# BuckConverter.net
KiCad netlist of a schematic drawn in Altium Designer
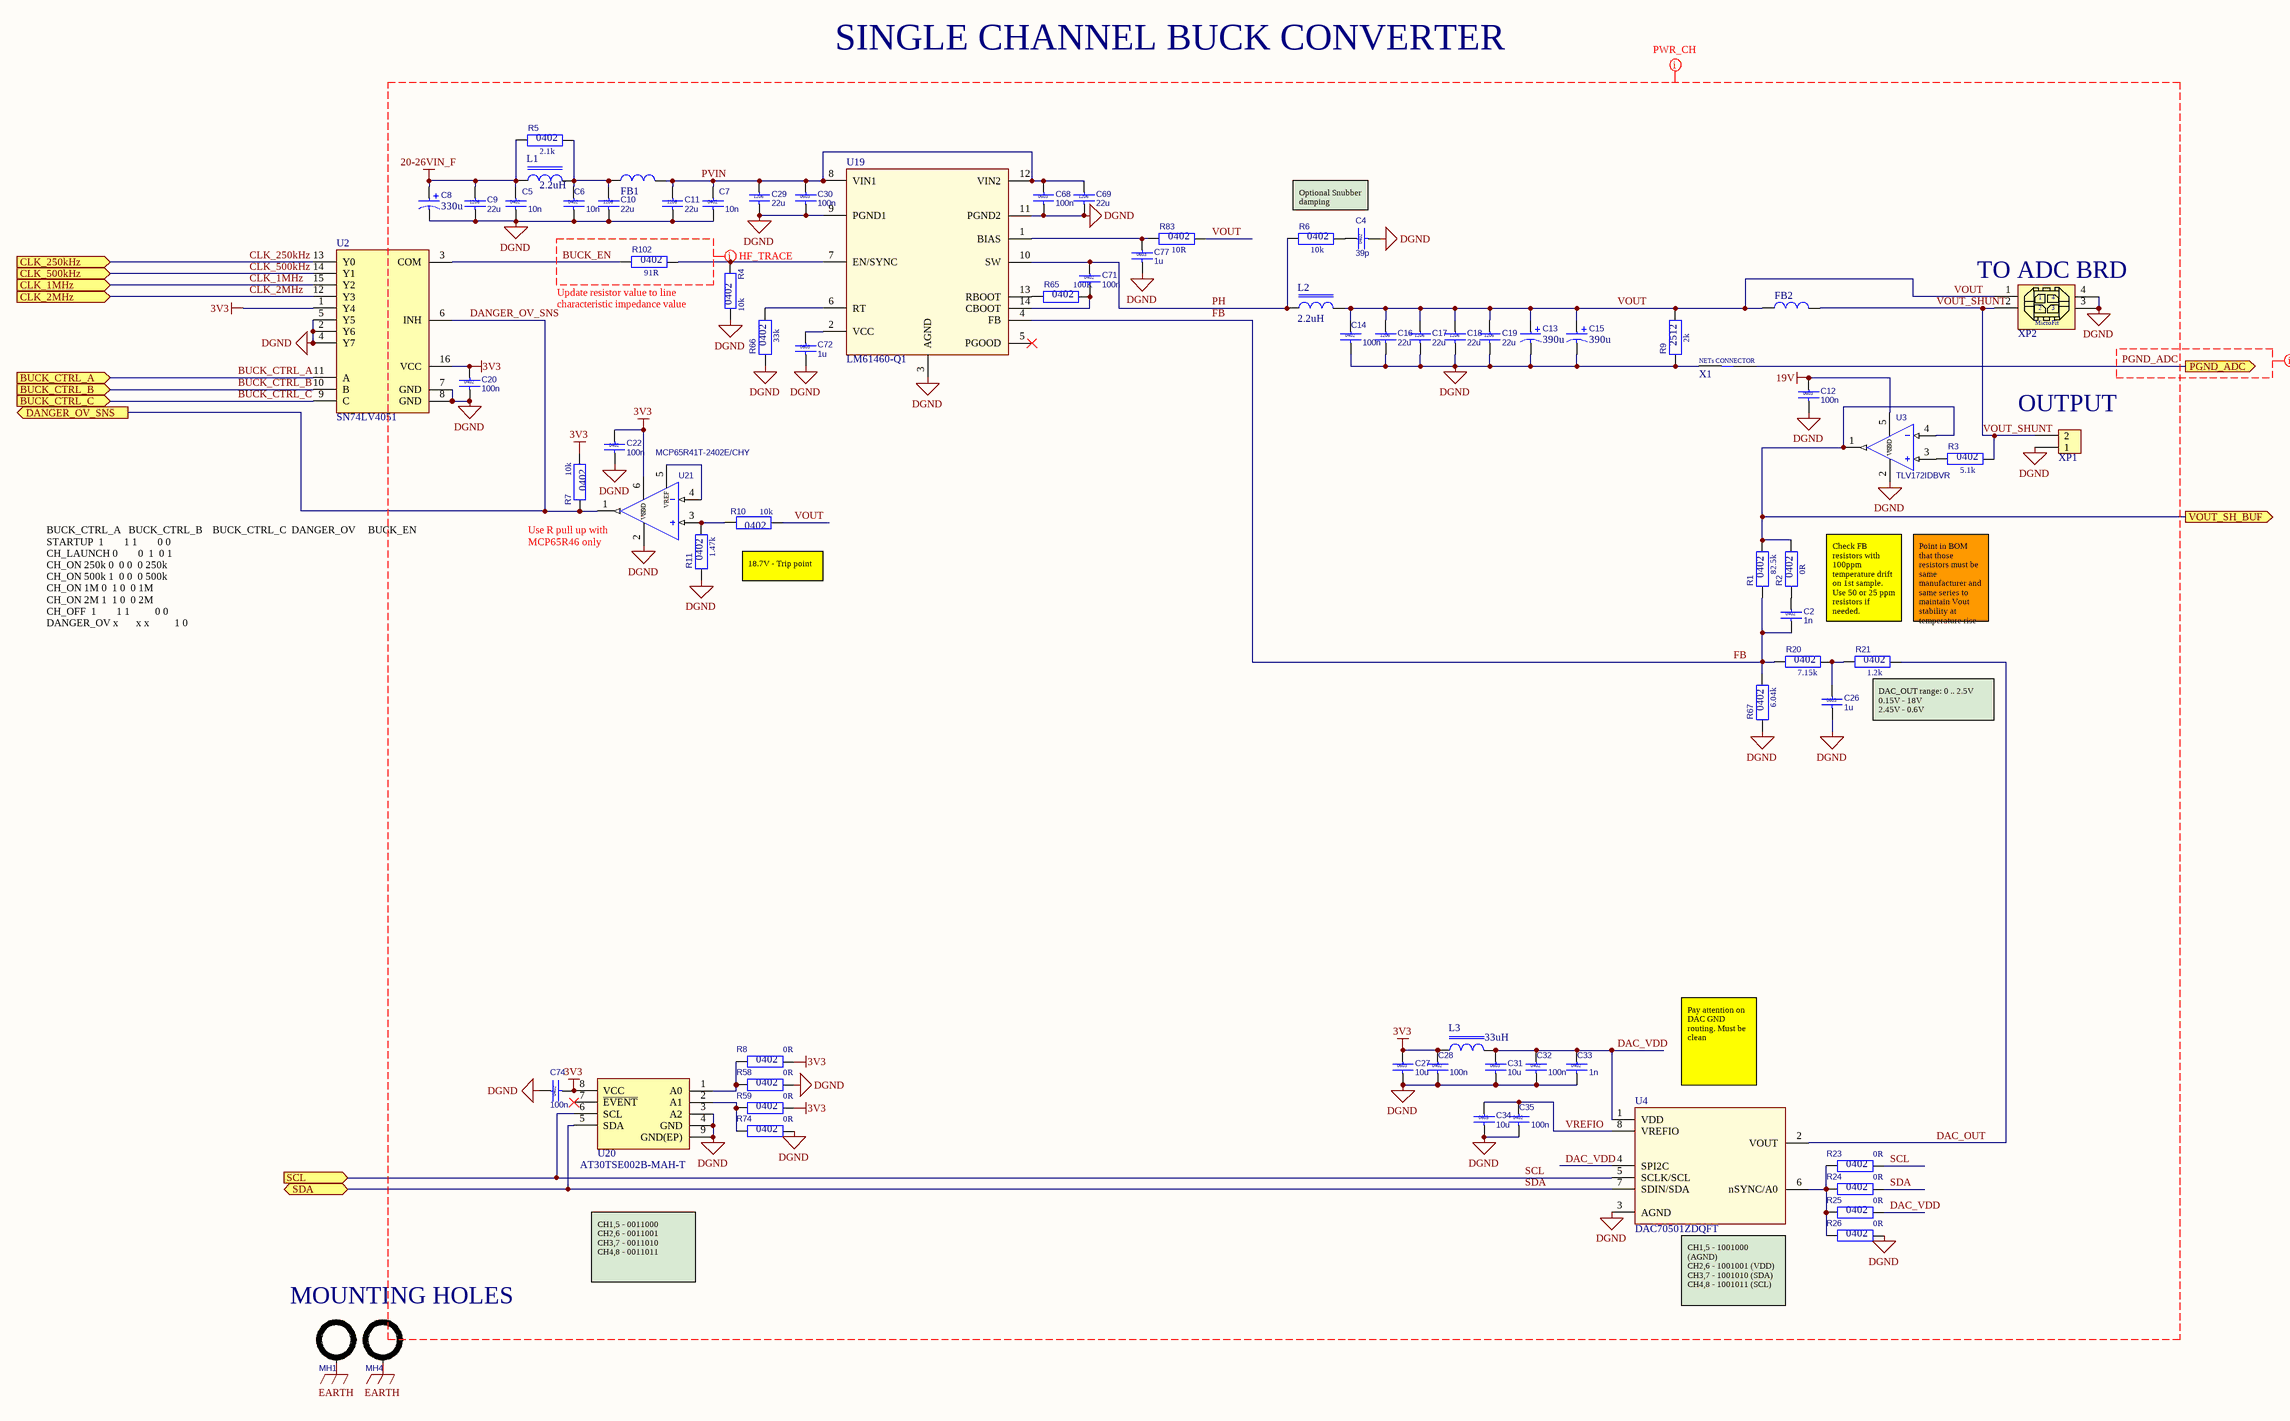
[diagram p0: BuckConverter.SchDoc]

(export (version "E")
  (design (tool "Eeschema 10.0.6"))
  (components
    (comp (ref "C2")
      (value "1n")
      (footprint "CC0402M")
      (description "Chip ceramic capacitor")
      (fields
        (field (name "CASE") "0402")
        (field (name "PARTNUMBER") "CC0402K-X7R-50V-1N-M")
        (field (name "MANUFACTURER") "Yageo")
        (field (name "PUBLISHER") "alexey.savchenko")
      )
      (libsource (lib "AltiumLib") (part "Capacitor_nonpolar"))
    )
    (comp (ref "C4")
      (value "39p")
      (footprint "CC0402M")
      (description "Chip ceramic capacitor")
      (fields
        (field (name "CASE") "0402")
        (field (name "PARTNUMBER") "CC0402J-NP0-50V-39P-M")
        (field (name "MANUFACTURER") "Yageo")
        (field (name "PUBLISHER") "alexey.savchenko")
      )
      (libsource (lib "AltiumLib") (part "Capacitor_nonpolar"))
    )
    (comp (ref "C5")
      (value "10n")
      (footprint "CC0603M")
      (description "Chip ceramic capacitor")
      (fields
        (field (name "CASE") "0402")
        (field (name "PARTNUMBER") "CC0402K-X7R-50V-10N-M")
        (field (name "MANUFACTURER") "Yageo")
        (field (name "PUBLISHER") "alexey.savchenko")
      )
      (libsource (lib "AltiumLib") (part "Capacitor_nonpolar"))
    )
    (comp (ref "C6")
      (value "10n")
      (footprint "CC0603M")
      (description "Chip ceramic capacitor")
      (fields
        (field (name "CASE") "0402")
        (field (name "PARTNUMBER") "CC0402K-X7R-50V-10N-M")
        (field (name "MANUFACTURER") "Yageo")
        (field (name "PUBLISHER") "alexey.savchenko")
      )
      (libsource (lib "AltiumLib") (part "Capacitor_nonpolar"))
    )
    (comp (ref "C7")
      (value "10n")
      (footprint "CC0603M")
      (description "Chip ceramic capacitor")
      (fields
        (field (name "CASE") "0402")
        (field (name "PARTNUMBER") "CC0402K-X7R-50V-10N-M")
        (field (name "MANUFACTURER") "Yageo")
        (field (name "PUBLISHER") "alexey.savchenko")
      )
      (libsource (lib "AltiumLib") (part "Capacitor_nonpolar"))
    )
    (comp (ref "C8")
      (value "330u")
      (footprint "CA-D10H10.5-SMD")
      (description "Aluminium Electrlytic capacitor")
      (fields
        (field (name "PARTNUMBER") "CE-L10D10-330U-35V-SMD")
        (field (name "MANUFACTURER") "Kemet")
        (field (name "PUBLISHER") "alexey.savchenko")
      )
      (libsource (lib "AltiumLib") (part "Capacitor_polar"))
    )
    (comp (ref "C9")
      (value "22u")
      (footprint "CC1206M")
      (description "Chip ceramic capacitor")
      (fields
        (field (name "CASE") "1206")
        (field (name "PARTNUMBER") "CC1206K-X5R-35V-22U-M")
        (field (name "MANUFACTURER") "TDK")
        (field (name "PUBLISHER") "alexey.savchenko")
      )
      (libsource (lib "AltiumLib") (part "Capacitor_nonpolar"))
    )
    (comp (ref "C10")
      (value "22u")
      (footprint "CC1206M")
      (description "Chip ceramic capacitor")
      (fields
        (field (name "CASE") "1206")
        (field (name "PARTNUMBER") "CC1206K-X5R-35V-22U-M")
        (field (name "MANUFACTURER") "TDK")
        (field (name "PUBLISHER") "alexey.savchenko")
      )
      (libsource (lib "AltiumLib") (part "Capacitor_nonpolar"))
    )
    (comp (ref "C11")
      (value "22u")
      (footprint "CC1206M")
      (description "Chip ceramic capacitor")
      (fields
        (field (name "CASE") "1206")
        (field (name "PARTNUMBER") "CC1206K-X5R-35V-22U-M")
        (field (name "MANUFACTURER") "TDK")
        (field (name "PUBLISHER") "alexey.savchenko")
      )
      (libsource (lib "AltiumLib") (part "Capacitor_nonpolar"))
    )
    (comp (ref "C12")
      (value "100n")
      (footprint "CC0603M")
      (description "Chip ceramic capacitor")
      (fields
        (field (name "CASE") "0603")
        (field (name "PARTNUMBER") "CC0603K-X7R-50V-100N-M")
        (field (name "MANUFACTURER") "Yageo")
        (field (name "PUBLISHER") "alexey.savchenko")
      )
      (libsource (lib "AltiumLib") (part "Capacitor_nonpolar"))
    )
    (comp (ref "C13")
      (value "390u")
      (footprint "CA-D10H13P5.0-THR")
      (description "Aluminium polymer capacitor")
      (fields
        (field (name "PARTNUMBER") "APSG250ELL391MJB5S")
        (field (name "MANUFACTURER") "United Chemi-Con")
        (field (name "PUBLISHER") "alexey.savchenko")
      )
      (libsource (lib "AltiumLib") (part "Capacitor_polar"))
    )
    (comp (ref "C14")
      (value "100n")
      (footprint "CC0402M")
      (description "Chip ceramic capacitor")
      (fields
        (field (name "CASE") "0402")
        (field (name "PARTNUMBER") "CC0402K-X7R-25V-100N-M")
        (field (name "MANUFACTURER") "Murata")
        (field (name "PUBLISHER") "alexey.savchenko")
      )
      (libsource (lib "AltiumLib") (part "Capacitor_nonpolar"))
    )
    (comp (ref "C15")
      (value "390u")
      (footprint "CA-D10H13P5.0-THR")
      (description "Aluminium polymer capacitor")
      (fields
        (field (name "PARTNUMBER") "APSG250ELL391MJB5S")
        (field (name "MANUFACTURER") "United Chemi-Con")
        (field (name "PUBLISHER") "alexey.savchenko")
      )
      (libsource (lib "AltiumLib") (part "Capacitor_polar"))
    )
    (comp (ref "C16")
      (value "22u")
      (footprint "CC1206M")
      (description "Chip ceramic capacitor")
      (fields
        (field (name "CASE") "1206")
        (field (name "PARTNUMBER") "CC1206K-X5R-25V-22U-M")
        (field (name "MANUFACTURER") "Samsung")
        (field (name "PUBLISHER") "alexey.savchenko")
      )
      (libsource (lib "AltiumLib") (part "Capacitor_nonpolar"))
    )
    (comp (ref "C17")
      (value "22u")
      (footprint "CC1206M")
      (description "Chip ceramic capacitor")
      (fields
        (field (name "CASE") "1206")
        (field (name "PARTNUMBER") "CC1206K-X5R-25V-22U-M")
        (field (name "MANUFACTURER") "Samsung")
        (field (name "PUBLISHER") "alexey.savchenko")
      )
      (libsource (lib "AltiumLib") (part "Capacitor_nonpolar"))
    )
    (comp (ref "C18")
      (value "22u")
      (footprint "CC1206M")
      (description "Chip ceramic capacitor")
      (fields
        (field (name "CASE") "1206")
        (field (name "PARTNUMBER") "CC1206K-X5R-25V-22U-M")
        (field (name "MANUFACTURER") "Samsung")
        (field (name "PUBLISHER") "alexey.savchenko")
      )
      (libsource (lib "AltiumLib") (part "Capacitor_nonpolar"))
    )
    (comp (ref "C19")
      (value "22u")
      (footprint "CC1206M")
      (description "Chip ceramic capacitor")
      (fields
        (field (name "CASE") "1206")
        (field (name "PARTNUMBER") "CC1206K-X5R-25V-22U-M")
        (field (name "MANUFACTURER") "Samsung")
        (field (name "PUBLISHER") "alexey.savchenko")
      )
      (libsource (lib "AltiumLib") (part "Capacitor_nonpolar"))
    )
    (comp (ref "C20")
      (value "100n")
      (footprint "CC0402M")
      (description "Chip ceramic capacitor")
      (fields
        (field (name "CASE") "0402")
        (field (name "PARTNUMBER") "CC0402K-X7R-25V-100N-M")
        (field (name "MANUFACTURER") "Murata")
        (field (name "PUBLISHER") "alexey.savchenko")
      )
      (libsource (lib "AltiumLib") (part "Capacitor_nonpolar"))
    )
    (comp (ref "C22")
      (value "100n")
      (footprint "CC0402M")
      (description "Chip ceramic capacitor")
      (fields
        (field (name "CASE") "0402")
        (field (name "PARTNUMBER") "CC0402K-X7R-25V-100N-M")
        (field (name "MANUFACTURER") "Murata")
        (field (name "PUBLISHER") "alexey.savchenko")
      )
      (libsource (lib "AltiumLib") (part "Capacitor_nonpolar"))
    )
    (comp (ref "C26")
      (value "1u")
      (footprint "CC0603M")
      (description "Chip ceramic capacitor")
      (fields
        (field (name "CASE") "0603")
        (field (name "PARTNUMBER") "CC0603K-X7R-10V-1U-M")
        (field (name "MANUFACTURER") "Samsung")
        (field (name "PUBLISHER") "alexey.savchenko")
      )
      (libsource (lib "AltiumLib") (part "Capacitor_nonpolar"))
    )
    (comp (ref "C27")
      (value "10u")
      (footprint "CC0603M")
      (description "Chip ceramic capacitor")
      (fields
        (field (name "CASE") "0603")
        (field (name "PARTNUMBER") "CC0603K-X5R-10V-10U-M")
        (field (name "MANUFACTURER") "Murata")
        (field (name "PUBLISHER") "alexey.savchenko")
      )
      (libsource (lib "AltiumLib") (part "Capacitor_nonpolar"))
    )
    (comp (ref "C28")
      (value "100n")
      (footprint "CC0402M")
      (description "Chip ceramic capacitor")
      (fields
        (field (name "CASE") "0402")
        (field (name "PARTNUMBER") "CC0402K-X7R-25V-100N-M")
        (field (name "MANUFACTURER") "Murata")
        (field (name "PUBLISHER") "alexey.savchenko")
      )
      (libsource (lib "AltiumLib") (part "Capacitor_nonpolar"))
    )
    (comp (ref "C29")
      (value "22u")
      (footprint "CC1206M")
      (description "Chip ceramic capacitor")
      (fields
        (field (name "CASE") "1206")
        (field (name "PARTNUMBER") "CC1206K-X5R-35V-22U-M")
        (field (name "MANUFACTURER") "TDK")
        (field (name "PUBLISHER") "alexey.savchenko")
      )
      (libsource (lib "AltiumLib") (part "Capacitor_nonpolar"))
    )
    (comp (ref "C30")
      (value "100n")
      (footprint "CC0603M")
      (description "Chip ceramic capacitor")
      (fields
        (field (name "CASE") "0603")
        (field (name "PARTNUMBER") "CC0603K-X7R-50V-100N-M")
        (field (name "MANUFACTURER") "Yageo")
        (field (name "PUBLISHER") "alexey.savchenko")
      )
      (libsource (lib "AltiumLib") (part "Capacitor_nonpolar"))
    )
    (comp (ref "C31")
      (value "10u")
      (footprint "CC0603M")
      (description "Chip ceramic capacitor")
      (fields
        (field (name "CASE") "0603")
        (field (name "PARTNUMBER") "CC0603K-X5R-10V-10U-M")
        (field (name "MANUFACTURER") "Murata")
        (field (name "PUBLISHER") "alexey.savchenko")
      )
      (libsource (lib "AltiumLib") (part "Capacitor_nonpolar"))
    )
    (comp (ref "C32")
      (value "100n")
      (footprint "CC0402M")
      (description "Chip ceramic capacitor")
      (fields
        (field (name "CASE") "0402")
        (field (name "PARTNUMBER") "CC0402K-X7R-25V-100N-M")
        (field (name "MANUFACTURER") "Murata")
        (field (name "PUBLISHER") "alexey.savchenko")
      )
      (libsource (lib "AltiumLib") (part "Capacitor_nonpolar"))
    )
    (comp (ref "C33")
      (value "1n")
      (footprint "CC0402M")
      (description "Chip ceramic capacitor")
      (fields
        (field (name "CASE") "0402")
        (field (name "PARTNUMBER") "CC0402K-X7R-50V-1N-M")
        (field (name "MANUFACTURER") "Yageo")
        (field (name "PUBLISHER") "alexey.savchenko")
      )
      (libsource (lib "AltiumLib") (part "Capacitor_nonpolar"))
    )
    (comp (ref "C34")
      (value "10u")
      (footprint "CC0603M")
      (description "Chip ceramic capacitor")
      (fields
        (field (name "CASE") "0603")
        (field (name "PARTNUMBER") "CC0603K-X5R-10V-10U-M")
        (field (name "MANUFACTURER") "Murata")
        (field (name "PUBLISHER") "alexey.savchenko")
      )
      (libsource (lib "AltiumLib") (part "Capacitor_nonpolar"))
    )
    (comp (ref "C35")
      (value "100n")
      (footprint "CC0402M")
      (description "Chip ceramic capacitor")
      (fields
        (field (name "CASE") "0402")
        (field (name "PARTNUMBER") "CC0402K-X7R-25V-100N-M")
        (field (name "MANUFACTURER") "Murata")
        (field (name "PUBLISHER") "alexey.savchenko")
      )
      (libsource (lib "AltiumLib") (part "Capacitor_nonpolar"))
    )
    (comp (ref "C68")
      (value "100n")
      (footprint "CC0603M")
      (description "Chip ceramic capacitor")
      (fields
        (field (name "CASE") "0603")
        (field (name "PARTNUMBER") "CC0603K-X7R-50V-100N-M")
        (field (name "MANUFACTURER") "Yageo")
        (field (name "PUBLISHER") "alexey.savchenko")
      )
      (libsource (lib "AltiumLib") (part "Capacitor_nonpolar"))
    )
    (comp (ref "C69")
      (value "22u")
      (footprint "CC1206M")
      (description "Chip ceramic capacitor")
      (fields
        (field (name "CASE") "1206")
        (field (name "PARTNUMBER") "CC1206K-X5R-35V-22U-M")
        (field (name "MANUFACTURER") "TDK")
        (field (name "PUBLISHER") "alexey.savchenko")
      )
      (libsource (lib "AltiumLib") (part "Capacitor_nonpolar"))
    )
    (comp (ref "C71")
      (value "100n")
      (footprint "CC0402M")
      (description "Chip ceramic capacitor")
      (fields
        (field (name "CASE") "0402")
        (field (name "PARTNUMBER") "CC0402K-X7R-25V-100N-M")
        (field (name "MANUFACTURER") "Murata")
        (field (name "PUBLISHER") "alexey.savchenko")
      )
      (libsource (lib "AltiumLib") (part "Capacitor_nonpolar"))
    )
    (comp (ref "C72")
      (value "1u")
      (footprint "CC0603M")
      (description "Chip ceramic capacitor")
      (fields
        (field (name "CASE") "0603")
        (field (name "PARTNUMBER") "CC0603K-X5R-50V-1U-M")
        (field (name "MANUFACTURER") "Samsung")
        (field (name "PUBLISHER") "alexey.savchenko")
      )
      (libsource (lib "AltiumLib") (part "Capacitor_nonpolar"))
    )
    (comp (ref "C74")
      (value "100n")
      (footprint "CC0402M")
      (description "Chip ceramic capacitor")
      (fields
        (field (name "CASE") "0402")
        (field (name "PARTNUMBER") "CC0402K-X7R-25V-100N-M")
        (field (name "MANUFACTURER") "Murata")
        (field (name "PUBLISHER") "alexey.savchenko")
      )
      (libsource (lib "AltiumLib") (part "Capacitor_nonpolar"))
    )
    (comp (ref "C77")
      (value "1u")
      (footprint "CC0603M")
      (description "Chip ceramic capacitor")
      (fields
        (field (name "CASE") "0603")
        (field (name "PARTNUMBER") "CC0603K-X5R-50V-1U-M")
        (field (name "MANUFACTURER") "Samsung")
        (field (name "PUBLISHER") "alexey.savchenko")
      )
      (libsource (lib "AltiumLib") (part "Capacitor_nonpolar"))
    )
    (comp (ref "FB1")
      (value "BLM21SP601SH1D")
      (footprint "FB0805M")
      (description "600 Ohms @ 100MHz 1 Power Line Ferrite Bead 0805 (2012 Metric) 2.3A")
      (fields (field (name "MANUFACTURER") "Murata") (field (name "PUBLISHER") "alexey.savchenko"))
      (libsource (lib "AltiumLib") (part "FerriteBead"))
    )
    (comp (ref "FB2")
      (value "BLM18KG260TN1D")
      (footprint "FB0603M")
      (description "26 Ohms @ 100MHz 1 Power Line Ferrite Bead 0603 (1608 Metric) 6A 7mOhm")
      (fields (field (name "MANUFACTURER") "Murata") (field (name "PUBLISHER") "alexey.savchenko"))
      (libsource (lib "AltiumLib") (part "FerriteBead"))
    )
    (comp (ref "L1")
      (value "2.2uH")
      (footprint "MGV252010S")
      (description "2.2µH Shielded Molded Inductor 2.4A 110mOhm Max 1008 (2520 Metric)")
      (fields
        (field (name "PARTNUMBER") "MGV252010S2R2M-10")
        (field (name "MANUFACTURER") "Laird-Signal Integrity Products")
        (field (name "PUBLISHER") "alexey.savchenko")
      )
      (libsource (lib "AltiumLib") (part "Inductor"))
    )
    (comp (ref "L2")
      (value "2.2uH")
      (footprint "104CDMCCDS")
      (description "FIXED IND 2.2UH 15A 7 MOHM")
      (fields
        (field (name "PARTNUMBER") "104CDMCCDS-2R2MC")
        (field (name "MANUFACTURER") "Sumida")
        (field (name "PUBLISHER") "alexey.savchenko")
      )
      (libsource (lib "AltiumLib") (part "Inductor"))
    )
    (comp (ref "L3")
      (value "33uH")
      (footprint "IC0805-M")
      (description "FIXED IND 33UH 5MA 1.25 OHM SMD")
      (fields
        (field (name "PARTNUMBER") "CV201210-330K")
        (field (name "MANUFACTURER") "Bourns")
        (field (name "PUBLISHER") "alexey.savchenko")
      )
      (libsource (lib "AltiumLib") (part "Inductor"))
    )
    (comp (ref "MH1")
      (value "MH-3.5-PLATED")
      (footprint "MH_3.5_PLATED")
      (description "Mounting Hole")
      (fields (field (name "MANUFACTURER") "NULL") (field (name "PUBLISHER") "alexey.savchenko"))
      (libsource (lib "AltiumLib") (part "MH_MISC"))
    )
    (comp (ref "MH4")
      (value "MH-3.5-PLATED")
      (footprint "MH_3.5_PLATED")
      (description "Mounting Hole")
      (fields (field (name "MANUFACTURER") "NULL") (field (name "PUBLISHER") "alexey.savchenko"))
      (libsource (lib "AltiumLib") (part "MH_MISC"))
    )
    (comp (ref "R1")
      (value "82.5k")
      (footprint "RC0402M")
      (description "Chip resistor")
      (fields
        (field (name "CASE") "0402")
        (field (name "PARTNUMBER") "RC0402F-82K5-M")
        (field (name "POWER") "0.063W")
        (field (name "PUBLISHER") "alexey.savchenko")
      )
      (libsource (lib "AltiumLib") (part "Resistor"))
    )
    (comp (ref "R2")
      (value "0R")
      (footprint "RC0402M")
      (description "Chip resistor")
      (fields
        (field (name "CASE") "0402")
        (field (name "PARTNUMBER") "RC0402F-0R-M")
        (field (name "MANUFACTURER") "Yageo")
        (field (name "PUBLISHER") "alexey.savchenko")
      )
      (libsource (lib "AltiumLib") (part "Resistor"))
    )
    (comp (ref "R3")
      (value "5.1k")
      (footprint "RC0402M")
      (description "Chip resistor")
      (fields
        (field (name "CASE") "0402")
        (field (name "PARTNUMBER") "RC0402F-5K1-M")
        (field (name "MANUFACTURER") "Yageo")
        (field (name "PUBLISHER") "alexey.savchenko")
      )
      (libsource (lib "AltiumLib") (part "Resistor"))
    )
    (comp (ref "R4")
      (value "10k")
      (footprint "RC0402M")
      (description "Chip resistor")
      (fields
        (field (name "CASE") "0402")
        (field (name "PARTNUMBER") "RC0402F-10K-M")
        (field (name "MANUFACTURER") "Yageo")
        (field (name "PUBLISHER") "alexey.savchenko")
      )
      (libsource (lib "AltiumLib") (part "Resistor"))
    )
    (comp (ref "R5")
      (value "2.1k")
      (footprint "RC0402M")
      (description "Chip resistor")
      (fields
        (field (name "CASE") "0402")
        (field (name "PARTNUMBER") "RC0402F-2K1-M")
        (field (name "POWER") "0.063W")
        (field (name "PUBLISHER") "alexey.savchenko")
      )
      (libsource (lib "AltiumLib") (part "Resistor"))
    )
    (comp (ref "R6")
      (value "10k")
      (footprint "RC0402M")
      (description "Chip resistor")
      (fields
        (field (name "CASE") "0402")
        (field (name "PARTNUMBER") "RC0402F-10K-M")
        (field (name "POWER") "0.063W")
        (field (name "PUBLISHER") "alexey.savchenko")
      )
      (libsource (lib "AltiumLib") (part "Resistor"))
    )
    (comp (ref "R7")
      (value "10k")
      (footprint "RC0402M")
      (description "Chip resistor")
      (fields
        (field (name "CASE") "0402")
        (field (name "PARTNUMBER") "RC0402F-10K-M")
        (field (name "MANUFACTURER") "Yageo")
        (field (name "PUBLISHER") "alexey.savchenko")
      )
      (libsource (lib "AltiumLib") (part "Resistor"))
    )
    (comp (ref "R8")
      (value "0R")
      (footprint "RC0402M")
      (description "Chip resistor")
      (fields
        (field (name "CASE") "0402")
        (field (name "PARTNUMBER") "RC0402F-0R-M")
        (field (name "POWER") "0.063W")
        (field (name "PUBLISHER") "alexey.savchenko")
      )
      (libsource (lib "AltiumLib") (part "Resistor"))
    )
    (comp (ref "R9")
      (value "2k")
      (footprint "RC2512M")
      (description "Chip resistor")
      (fields
        (field (name "CASE") "2512")
        (field (name "PARTNUMBER") "RC2512J-2K0-M")
        (field (name "MANUFACTURER") "Stackpole")
        (field (name "PUBLISHER") "alexey.savchenko")
      )
      (libsource (lib "AltiumLib") (part "Resistor"))
    )
    (comp (ref "R10")
      (value "10k")
      (footprint "RC0402M")
      (description "Chip resistor")
      (fields
        (field (name "CASE") "0402")
        (field (name "PARTNUMBER") "RC0402F-10K-M")
        (field (name "MANUFACTURER") "Yageo")
        (field (name "PUBLISHER") "alexey.savchenko")
      )
      (libsource (lib "AltiumLib") (part "Resistor"))
    )
    (comp (ref "R11")
      (value "1.47k")
      (footprint "RC0402M")
      (description "Chip resistor")
      (fields
        (field (name "CASE") "0402")
        (field (name "PARTNUMBER") "RC0402F-1K47-M")
        (field (name "MANUFACTURER") "Yageo")
        (field (name "PUBLISHER") "alexey.savchenko")
      )
      (libsource (lib "AltiumLib") (part "Resistor"))
    )
    (comp (ref "R20")
      (value "7.15k")
      (footprint "RC0402M")
      (description "Chip resistor")
      (fields
        (field (name "CASE") "0402")
        (field (name "PARTNUMBER") "RC0402F-7K15-M")
        (field (name "MANUFACTURER") "Yageo")
        (field (name "PUBLISHER") "alexey.savchenko")
      )
      (libsource (lib "AltiumLib") (part "Resistor"))
    )
    (comp (ref "R21")
      (value "1.2k")
      (footprint "RC0402M")
      (description "Chip resistor")
      (fields
        (field (name "CASE") "0402")
        (field (name "PARTNUMBER") "RC0402F-1K2-M")
        (field (name "MANUFACTURER") "Yageo")
        (field (name "PUBLISHER") "alexey.savchenko")
      )
      (libsource (lib "AltiumLib") (part "Resistor"))
    )
    (comp (ref "R23")
      (value "0R")
      (footprint "RC0402M")
      (description "Chip resistor")
      (fields
        (field (name "CASE") "0402")
        (field (name "PARTNUMBER") "RC0402F-0R-M")
        (field (name "POWER") "0.063W")
        (field (name "PUBLISHER") "alexey.savchenko")
      )
      (libsource (lib "AltiumLib") (part "Resistor"))
    )
    (comp (ref "R24")
      (value "0R")
      (footprint "RC0402M")
      (description "Chip resistor")
      (fields
        (field (name "CASE") "0402")
        (field (name "PARTNUMBER") "RC0402F-0R-M")
        (field (name "POWER") "0.063W")
        (field (name "PUBLISHER") "alexey.savchenko")
      )
      (libsource (lib "AltiumLib") (part "Resistor"))
    )
    (comp (ref "R25")
      (value "0R")
      (footprint "RC0402M")
      (description "Chip resistor")
      (fields
        (field (name "CASE") "0402")
        (field (name "PARTNUMBER") "RC0402F-0R-M")
        (field (name "POWER") "0.063W")
        (field (name "PUBLISHER") "alexey.savchenko")
      )
      (libsource (lib "AltiumLib") (part "Resistor"))
    )
    (comp (ref "R26")
      (value "0R")
      (footprint "RC0402M")
      (description "Chip resistor")
      (fields
        (field (name "CASE") "0402")
        (field (name "PARTNUMBER") "RC0402F-0R-M")
        (field (name "POWER") "0.063W")
        (field (name "PUBLISHER") "alexey.savchenko")
      )
      (libsource (lib "AltiumLib") (part "Resistor"))
    )
    (comp (ref "R58")
      (value "0R")
      (footprint "RC0402M")
      (description "Chip resistor")
      (fields
        (field (name "CASE") "0402")
        (field (name "PARTNUMBER") "RC0402F-0R-M")
        (field (name "POWER") "0.063W")
        (field (name "PUBLISHER") "alexey.savchenko")
      )
      (libsource (lib "AltiumLib") (part "Resistor"))
    )
    (comp (ref "R59")
      (value "0R")
      (footprint "RC0402M")
      (description "Chip resistor")
      (fields
        (field (name "CASE") "0402")
        (field (name "PARTNUMBER") "RC0402F-0R-M")
        (field (name "POWER") "0.063W")
        (field (name "PUBLISHER") "alexey.savchenko")
      )
      (libsource (lib "AltiumLib") (part "Resistor"))
    )
    (comp (ref "R65")
      (value "100R")
      (footprint "RC0402M")
      (description "Chip resistor")
      (fields
        (field (name "CASE") "0402")
        (field (name "PARTNUMBER") "RC0402F-100R-M")
        (field (name "MANUFACTURER") "Yageo")
        (field (name "PUBLISHER") "alexey.savchenko")
      )
      (libsource (lib "AltiumLib") (part "Resistor"))
    )
    (comp (ref "R66")
      (value "33k")
      (footprint "RC0402M")
      (description "Chip resistor")
      (fields
        (field (name "CASE") "0402")
        (field (name "PARTNUMBER") "RC0402F-33K-M")
        (field (name "MANUFACTURER") "Yageo")
        (field (name "PUBLISHER") "alexey.savchenko")
      )
      (libsource (lib "AltiumLib") (part "Resistor"))
    )
    (comp (ref "R67")
      (value "6.04k")
      (footprint "RC0402M")
      (description "Chip resistor")
      (fields
        (field (name "CASE") "0402")
        (field (name "PARTNUMBER") "RC0402F-6K04-M")
        (field (name "MANUFACTURER") "Yageo")
        (field (name "PUBLISHER") "alexey.savchenko")
      )
      (libsource (lib "AltiumLib") (part "Resistor"))
    )
    (comp (ref "R74")
      (value "0R")
      (footprint "RC0402M")
      (description "Chip resistor")
      (fields
        (field (name "CASE") "0402")
        (field (name "PARTNUMBER") "RC0402F-0R-M")
        (field (name "POWER") "0.063W")
        (field (name "PUBLISHER") "alexey.savchenko")
      )
      (libsource (lib "AltiumLib") (part "Resistor"))
    )
    (comp (ref "R83")
      (value "10R")
      (footprint "RC0402M")
      (description "Chip resistor")
      (fields
        (field (name "CASE") "0402")
        (field (name "PARTNUMBER") "RC0402F-10R-M")
        (field (name "MANUFACTURER") "Yageo")
        (field (name "PUBLISHER") "alexey.savchenko")
      )
      (libsource (lib "AltiumLib") (part "Resistor"))
    )
    (comp (ref "R102")
      (value "91R")
      (footprint "RC0402M")
      (description "Chip resistor")
      (fields
        (field (name "CASE") "0402")
        (field (name "PARTNUMBER") "RC0402F-91R-M")
        (field (name "POWER") "0.063W")
        (field (name "PUBLISHER") "alexey.savchenko")
      )
      (libsource (lib "AltiumLib") (part "Resistor"))
    )
    (comp (ref "U2")
      (value "SN74LV4051")
      (footprint "TSSOP-16")
      (description "1 Circuit IC Switch 8:1 75Ohm 16-TSSOP")
      (fields
        (field (name "PARTNUMBER") "SN74LV4051AQPWRQ1")
        (field (name "MANUFACTURER") "TI")
        (field (name "PUBLISHER") "alexey.savchenko")
      )
      (libsource (lib "AltiumLib") (part "SN74LV4051"))
    )
    (comp (ref "U3")
      (value "TLV172IDBVR")
      (footprint "SOT23-5")
      (description "General Purpose Amplifier 1 Circuit Rail-to-Rail SOT-23-5")
      (fields (field (name "MANUFACTURER") "TI") (field (name "PUBLISHER") "alexey.savchenko"))
      (libsource (lib "AltiumLib") (part "TLV172IDBV"))
    )
    (comp (ref "U4")
      (value "DAC70501ZDQFT")
      (footprint "WSON-8")
      (description "SINGLE CHAN DAC 14BIT- ZEROCODE")
      (fields (field (name "MANUFACTURER") "TI") (field (name "PUBLISHER") "alexey.savchenko"))
      (libsource (lib "AltiumLib") (part "DACx0501"))
    )
    (comp (ref "U19")
      (value "LM61460-Q1")
      (footprint "VQFN-HR-14")
      (description "Buck Switching Regulator IC Positive Adjustable 1V 1 Output 6A 14-VFQFN")
      (fields (field (name "MANUFACTURER") "TI") (field (name "PUBLISHER") "alexey.savchenko"))
      (libsource (lib "AltiumLib") (part "LM61460-Q1"))
    )
    (comp (ref "U20")
      (value "AT30TSE002B-MAH-T")
      (footprint "WDFN-8")
      (description "Temperature Sensor Digital, Local -20°C ~ 125°C 10 b 8-WDFN (2x3)")
      (fields (field (name "MANUFACTURER") "Microchip") (field (name "PUBLISHER") "alexey.savchenko"))
      (libsource (lib "AltiumLib") (part "AT30TSE002B"))
    )
    (comp (ref "U21")
      (value "MCP65R41T-2402E/CHY")
      (footprint "SOT23-6")
      (description "IC COMPARATOR 2.4V REF SOT-23-6")
      (fields (field (name "MANUFACTURER") "Microchip") (field (name "PUBLISHER") "alexey.savchenko"))
      (libsource (lib "AltiumLib") (part "MCP65R41T"))
    )
    (comp (ref "X1")
      (value "NETs_CONNECTOR")
      (footprint "NETs_CONNECTOR")
      (description "No BOM component to short circuit 2 nets")
      (fields (field (name "MANUFACTURER") "NULL") (field (name "PUBLISHER") "alexey.savchenko"))
      (libsource (lib "AltiumLib") (part "NETs_CONNECTOR"))
    )
    (comp (ref "XP1")
      (value "TBH-2x3.81P-RA-GN")
      (footprint "TBH-2x3.81P-RA-GN")
      (fields (field (name "MANUFACTURER") "Würth Elektronik") (field (name "PUBLISHER") "alexey.savchenko"))
      (libsource (lib "AltiumLib") (part "TBH-2x"))
    )
    (comp (ref "XP2")
      (value "0447690401")
      (footprint "0447690401")
      (fields (field (name "MANUFACTURER") "Molex") (field (name "PUBLISHER") "alexey.savchenko"))
      (libsource (lib "AltiumLib") (part "MicroFit-2x2"))
    )
  )
  (nets
    (net (code "1") (name "/BUCK_CTRL_A") (class "Default")
      (node (ref "U2") (pin "11") (pinfunction "A_11") (pintype "passive"))
    )
    (net (code "2") (name "/BUCK_CTRL_B") (class "Default")
      (node (ref "U2") (pin "10") (pinfunction "B_10") (pintype "passive"))
    )
    (net (code "3") (name "/BUCK_CTRL_C") (class "Default")
      (node (ref "U2") (pin "9") (pinfunction "C_9") (pintype "passive"))
    )
    (net (code "4") (name "/BUCK_EN") (class "Default")
      (node (ref "R102") (pin "1") (pinfunction "1_1") (pintype "passive"))
      (node (ref "U2") (pin "3") (pinfunction "COM_3") (pintype "passive"))
    )
    (net (code "5") (name "/CLK_1MHz") (class "Default")
      (node (ref "U2") (pin "15") (pinfunction "Y2_15") (pintype "passive"))
    )
    (net (code "6") (name "/CLK_2MHz") (class "Default")
      (node (ref "U2") (pin "12") (pinfunction "Y3_12") (pintype "passive"))
    )
    (net (code "7") (name "/CLK_250kHz") (class "Default")
      (node (ref "U2") (pin "13") (pinfunction "Y0_13") (pintype "passive"))
    )
    (net (code "8") (name "/CLK_500kHz") (class "Default")
      (node (ref "U2") (pin "14") (pinfunction "Y1_14") (pintype "passive"))
    )
    (net (code "9") (name "/DAC_OUT") (class "Default")
      (node (ref "R21") (pin "2") (pinfunction "2_2") (pintype "passive"))
      (node (ref "U4") (pin "2") (pinfunction "VOUT_2") (pintype "passive"))
    )
    (net (code "10") (name "/DAC_VDD") (class "Default")
      (node (ref "C31") (pin "1") (pinfunction "1_1") (pintype "passive"))
      (node (ref "C32") (pin "1") (pinfunction "1_1") (pintype "passive"))
      (node (ref "C33") (pin "1") (pinfunction "1_1") (pintype "passive"))
      (node (ref "L3") (pin "2") (pinfunction "2_2") (pintype "passive"))
      (node (ref "R25") (pin "2") (pinfunction "2_2") (pintype "passive"))
      (node (ref "U4") (pin "1") (pinfunction "VDD_1") (pintype "passive"))
      (node (ref "U4") (pin "4") (pinfunction "SPI2C_4") (pintype "passive"))
    )
    (net (code "11") (name "/DANGER_OV_SNS") (class "Default")
      (node (ref "R7") (pin "1") (pinfunction "1_1") (pintype "passive"))
      (node (ref "U2") (pin "6") (pinfunction "INH_6") (pintype "passive"))
      (node (ref "U21") (pin "1") (pinfunction "OUT1_1") (pintype "output"))
    )
    (net (code "12") (name "/FB") (class "Default")
      (node (ref "C2") (pin "2") (pinfunction "2_2") (pintype "passive"))
      (node (ref "R1") (pin "1") (pinfunction "1_1") (pintype "passive"))
      (node (ref "R20") (pin "1") (pinfunction "1_1") (pintype "passive"))
      (node (ref "R67") (pin "2") (pinfunction "2_2") (pintype "passive"))
      (node (ref "U19") (pin "4") (pinfunction "FB_4") (pintype "passive"))
    )
    (net (code "13") (name "/PGND_ADC") (class "Default")
      (node (ref "X1") (pin "2") (pinfunction "2_2") (pintype "passive"))
    )
    (net (code "14") (name "/PH") (class "Default")
      (node (ref "C71") (pin "1") (pinfunction "1_1") (pintype "passive"))
      (node (ref "L2") (pin "1") (pinfunction "1_1") (pintype "passive"))
      (node (ref "R6") (pin "1") (pinfunction "1_1") (pintype "passive"))
      (node (ref "U19") (pin "10") (pinfunction "SW_10") (pintype "passive"))
    )
    (net (code "15") (name "/PVIN") (class "Default")
      (node (ref "C11") (pin "1") (pinfunction "1_1") (pintype "passive"))
      (node (ref "C29") (pin "1") (pinfunction "1_1") (pintype "passive"))
      (node (ref "C30") (pin "1") (pinfunction "1_1") (pintype "passive"))
      (node (ref "C68") (pin "1") (pinfunction "1_1") (pintype "passive"))
      (node (ref "C69") (pin "1") (pinfunction "1_1") (pintype "passive"))
      (node (ref "C7") (pin "1") (pinfunction "1_1") (pintype "passive"))
      (node (ref "FB1") (pin "2") (pinfunction "2_2") (pintype "passive"))
      (node (ref "U19") (pin "12") (pinfunction "VIN2_12") (pintype "passive"))
      (node (ref "U19") (pin "8") (pinfunction "VIN1_8") (pintype "passive"))
    )
    (net (code "16") (name "/SCL") (class "Default")
      (node (ref "R23") (pin "2") (pinfunction "2_2") (pintype "passive"))
      (node (ref "U20") (pin "6") (pinfunction "SCL_6") (pintype "passive"))
      (node (ref "U4") (pin "5") (pinfunction "SCLK/SCL_5") (pintype "passive"))
    )
    (net (code "17") (name "/SDA") (class "Default")
      (node (ref "R24") (pin "2") (pinfunction "2_2") (pintype "passive"))
      (node (ref "U20") (pin "5") (pinfunction "SDA_5") (pintype "passive"))
      (node (ref "U4") (pin "7") (pinfunction "SDIN/SDA_7") (pintype "passive"))
    )
    (net (code "18") (name "/VOUT") (class "Default")
      (node (ref "C13") (pin "1") (pinfunction "1_1") (pintype "passive"))
      (node (ref "C14") (pin "1") (pinfunction "1_1") (pintype "passive"))
      (node (ref "C15") (pin "1") (pinfunction "1_1") (pintype "passive"))
      (node (ref "C16") (pin "1") (pinfunction "1_1") (pintype "passive"))
      (node (ref "C17") (pin "1") (pinfunction "1_1") (pintype "passive"))
      (node (ref "C18") (pin "1") (pinfunction "1_1") (pintype "passive"))
      (node (ref "C19") (pin "1") (pinfunction "1_1") (pintype "passive"))
      (node (ref "FB2") (pin "1") (pinfunction "1_1") (pintype "passive"))
      (node (ref "L2") (pin "2") (pinfunction "2_2") (pintype "passive"))
      (node (ref "R10") (pin "2") (pinfunction "2_2") (pintype "passive"))
      (node (ref "R83") (pin "2") (pinfunction "2_2") (pintype "passive"))
      (node (ref "R9") (pin "2") (pinfunction "2_2") (pintype "passive"))
      (node (ref "XP2") (pin "1") (pinfunction "1_1") (pintype "passive"))
    )
    (net (code "19") (name "/VOUT_SHUNT") (class "Default")
      (node (ref "FB2") (pin "2") (pinfunction "2_2") (pintype "passive"))
      (node (ref "R3") (pin "2") (pinfunction "2_2") (pintype "passive"))
      (node (ref "XP1") (pin "2") (pinfunction "2_2") (pintype "passive"))
      (node (ref "XP2") (pin "2") (pinfunction "2_2") (pintype "passive"))
    )
    (net (code "20") (name "/VOUT_SH_BUF") (class "Default")
      (node (ref "R1") (pin "2") (pinfunction "2_2") (pintype "passive"))
      (node (ref "R2") (pin "2") (pinfunction "2_2") (pintype "passive"))
      (node (ref "U3") (pin "1") (pinfunction "OUT1_1") (pintype "output"))
      (node (ref "U3") (pin "4") (pinfunction "IN1-_4") (pintype "input"))
    )
    (net (code "21") (name "/VREFIO") (class "Default")
      (node (ref "C34") (pin "1") (pinfunction "1_1") (pintype "passive"))
      (node (ref "C35") (pin "1") (pinfunction "1_1") (pintype "passive"))
      (node (ref "U4") (pin "8") (pinfunction "VREFIO_8") (pintype "passive"))
    )
    (net (code "22") (name "3V3") (class "Default")
      (node (ref "C20") (pin "1") (pinfunction "1_1") (pintype "passive"))
      (node (ref "C22") (pin "1") (pinfunction "1_1") (pintype "passive"))
      (node (ref "C27") (pin "1") (pinfunction "1_1") (pintype "passive"))
      (node (ref "C28") (pin "1") (pinfunction "1_1") (pintype "passive"))
      (node (ref "C74") (pin "2") (pinfunction "2_2") (pintype "passive"))
      (node (ref "L3") (pin "1") (pinfunction "1_1") (pintype "passive"))
      (node (ref "R59") (pin "2") (pinfunction "2_2") (pintype "passive"))
      (node (ref "R7") (pin "2") (pinfunction "2_2") (pintype "passive"))
      (node (ref "R8") (pin "2") (pinfunction "2_2") (pintype "passive"))
      (node (ref "U2") (pin "1") (pinfunction "Y4_1") (pintype "passive"))
      (node (ref "U2") (pin "16") (pinfunction "VCC_16") (pintype "power_in"))
      (node (ref "U20") (pin "8") (pinfunction "VCC_8") (pintype "passive"))
      (node (ref "U21") (pin "6") (pinfunction "VDD_6") (pintype "power_in"))
    )
    (net (code "23") (name "19V") (class "Default")
      (node (ref "C12") (pin "1") (pinfunction "1_1") (pintype "passive"))
      (node (ref "U3") (pin "5") (pinfunction "VDD_5") (pintype "power_in"))
    )
    (net (code "24") (name "20-26VIN_F") (class "Default")
      (node (ref "C5") (pin "1") (pinfunction "1_1") (pintype "passive"))
      (node (ref "C8") (pin "1") (pinfunction "1_1") (pintype "passive"))
      (node (ref "C9") (pin "1") (pinfunction "1_1") (pintype "passive"))
      (node (ref "L1") (pin "1") (pinfunction "1_1") (pintype "passive"))
      (node (ref "R5") (pin "1") (pinfunction "1_1") (pintype "passive"))
    )
    (net (code "25") (name "DGND") (class "Default")
      (node (ref "C10") (pin "2") (pinfunction "2_2") (pintype "passive"))
      (node (ref "C11") (pin "2") (pinfunction "2_2") (pintype "passive"))
      (node (ref "C12") (pin "2") (pinfunction "2_2") (pintype "passive"))
      (node (ref "C13") (pin "2") (pinfunction "2_2") (pintype "passive"))
      (node (ref "C14") (pin "2") (pinfunction "2_2") (pintype "passive"))
      (node (ref "C15") (pin "2") (pinfunction "2_2") (pintype "passive"))
      (node (ref "C16") (pin "2") (pinfunction "2_2") (pintype "passive"))
      (node (ref "C17") (pin "2") (pinfunction "2_2") (pintype "passive"))
      (node (ref "C18") (pin "2") (pinfunction "2_2") (pintype "passive"))
      (node (ref "C19") (pin "2") (pinfunction "2_2") (pintype "passive"))
      (node (ref "C20") (pin "2") (pinfunction "2_2") (pintype "passive"))
      (node (ref "C22") (pin "2") (pinfunction "2_2") (pintype "passive"))
      (node (ref "C26") (pin "2") (pinfunction "2_2") (pintype "passive"))
      (node (ref "C27") (pin "2") (pinfunction "2_2") (pintype "passive"))
      (node (ref "C28") (pin "2") (pinfunction "2_2") (pintype "passive"))
      (node (ref "C29") (pin "2") (pinfunction "2_2") (pintype "passive"))
      (node (ref "C30") (pin "2") (pinfunction "2_2") (pintype "passive"))
      (node (ref "C31") (pin "2") (pinfunction "2_2") (pintype "passive"))
      (node (ref "C32") (pin "2") (pinfunction "2_2") (pintype "passive"))
      (node (ref "C33") (pin "2") (pinfunction "2_2") (pintype "passive"))
      (node (ref "C34") (pin "2") (pinfunction "2_2") (pintype "passive"))
      (node (ref "C35") (pin "2") (pinfunction "2_2") (pintype "passive"))
      (node (ref "C4") (pin "2") (pinfunction "2_2") (pintype "passive"))
      (node (ref "C5") (pin "2") (pinfunction "2_2") (pintype "passive"))
      (node (ref "C6") (pin "2") (pinfunction "2_2") (pintype "passive"))
      (node (ref "C68") (pin "2") (pinfunction "2_2") (pintype "passive"))
      (node (ref "C69") (pin "2") (pinfunction "2_2") (pintype "passive"))
      (node (ref "C7") (pin "2") (pinfunction "2_2") (pintype "passive"))
      (node (ref "C72") (pin "2") (pinfunction "2_2") (pintype "passive"))
      (node (ref "C74") (pin "1") (pinfunction "1_1") (pintype "passive"))
      (node (ref "C77") (pin "2") (pinfunction "2_2") (pintype "passive"))
      (node (ref "C8") (pin "2") (pinfunction "2_2") (pintype "passive"))
      (node (ref "C9") (pin "2") (pinfunction "2_2") (pintype "passive"))
      (node (ref "R11") (pin "1") (pinfunction "1_1") (pintype "passive"))
      (node (ref "R26") (pin "2") (pinfunction "2_2") (pintype "passive"))
      (node (ref "R4") (pin "2") (pinfunction "2_2") (pintype "passive"))
      (node (ref "R58") (pin "2") (pinfunction "2_2") (pintype "passive"))
      (node (ref "R66") (pin "1") (pinfunction "1_1") (pintype "passive"))
      (node (ref "R67") (pin "1") (pinfunction "1_1") (pintype "passive"))
      (node (ref "R74") (pin "2") (pinfunction "2_2") (pintype "passive"))
      (node (ref "R9") (pin "1") (pinfunction "1_1") (pintype "passive"))
      (node (ref "U19") (pin "11") (pinfunction "PGND2_11") (pintype "passive"))
      (node (ref "U19") (pin "3") (pinfunction "AGND_3") (pintype "passive"))
      (node (ref "U19") (pin "9") (pinfunction "PGND1_9") (pintype "passive"))
      (node (ref "U2") (pin "2") (pinfunction "Y6_2") (pintype "passive"))
      (node (ref "U2") (pin "4") (pinfunction "Y7_4") (pintype "passive"))
      (node (ref "U2") (pin "5") (pinfunction "Y5_5") (pintype "passive"))
      (node (ref "U2") (pin "7") (pinfunction "GND_7") (pintype "power_in"))
      (node (ref "U2") (pin "8") (pinfunction "GND_8") (pintype "power_in"))
      (node (ref "U20") (pin "3") (pinfunction "A2_3") (pintype "passive"))
      (node (ref "U20") (pin "4") (pinfunction "GND_4") (pintype "passive"))
      (node (ref "U20") (pin "9") (pinfunction "GND(EP)_9") (pintype "passive"))
      (node (ref "U21") (pin "2") (pinfunction "VSS_2") (pintype "power_in"))
      (node (ref "U3") (pin "2") (pinfunction "VSS_2") (pintype "power_in"))
      (node (ref "U4") (pin "3") (pinfunction "AGND_3") (pintype "passive"))
      (node (ref "X1") (pin "1") (pinfunction "1_1") (pintype "passive"))
      (node (ref "XP1") (pin "1") (pinfunction "1_1") (pintype "passive"))
      (node (ref "XP2") (pin "3") (pinfunction "3_3") (pintype "passive"))
      (node (ref "XP2") (pin "4") (pinfunction "4_4") (pintype "passive"))
    )
    (net (code "26") (name "EARTH") (class "Default")
      (node (ref "MH1") (pin "0") (pinfunction "0_0") (pintype "passive"))
      (node (ref "MH4") (pin "0") (pinfunction "0_0") (pintype "passive"))
    )
    (net (code "27") (name "Net-(C2-Pad1)") (class "Default")
      (node (ref "C2") (pin "1") (pinfunction "1_1") (pintype "passive"))
      (node (ref "R2") (pin "1") (pinfunction "1_1") (pintype "passive"))
    )
    (net (code "28") (name "Net-(C4-Pad1)") (class "Default")
      (node (ref "C4") (pin "1") (pinfunction "1_1") (pintype "passive"))
      (node (ref "R6") (pin "2") (pinfunction "2_2") (pintype "passive"))
    )
    (net (code "29") (name "Net-(C10-Pad1)") (class "Default")
      (node (ref "C10") (pin "1") (pinfunction "1_1") (pintype "passive"))
      (node (ref "C6") (pin "1") (pinfunction "1_1") (pintype "passive"))
      (node (ref "FB1") (pin "1") (pinfunction "1_1") (pintype "passive"))
      (node (ref "L1") (pin "2") (pinfunction "2_2") (pintype "passive"))
      (node (ref "R5") (pin "2") (pinfunction "2_2") (pintype "passive"))
    )
    (net (code "30") (name "Net-(C26-Pad1)") (class "Default")
      (node (ref "C26") (pin "1") (pinfunction "1_1") (pintype "passive"))
      (node (ref "R20") (pin "2") (pinfunction "2_2") (pintype "passive"))
      (node (ref "R21") (pin "1") (pinfunction "1_1") (pintype "passive"))
    )
    (net (code "31") (name "Net-(U3-IN1+)") (class "Default")
      (node (ref "R3") (pin "1") (pinfunction "1_1") (pintype "passive"))
      (node (ref "U3") (pin "3") (pinfunction "IN1+_3") (pintype "input"))
    )
    (net (code "32") (name "Net-(U4-nSYNC{slash}A0)") (class "Default")
      (node (ref "R23") (pin "1") (pinfunction "1_1") (pintype "passive"))
      (node (ref "R24") (pin "1") (pinfunction "1_1") (pintype "passive"))
      (node (ref "R25") (pin "1") (pinfunction "1_1") (pintype "passive"))
      (node (ref "R26") (pin "1") (pinfunction "1_1") (pintype "passive"))
      (node (ref "U4") (pin "6") (pinfunction "nSYNC/A0_6") (pintype "passive"))
    )
    (net (code "33") (name "Net-(U19-BIAS)") (class "Default")
      (node (ref "C77") (pin "1") (pinfunction "1_1") (pintype "passive"))
      (node (ref "R83") (pin "1") (pinfunction "1_1") (pintype "passive"))
      (node (ref "U19") (pin "1") (pinfunction "BIAS_1") (pintype "passive"))
    )
    (net (code "34") (name "Net-(U19-CBOOT)") (class "Default")
      (node (ref "C71") (pin "2") (pinfunction "2_2") (pintype "passive"))
      (node (ref "R65") (pin "2") (pinfunction "2_2") (pintype "passive"))
      (node (ref "U19") (pin "14") (pinfunction "CBOOT_14") (pintype "passive"))
    )
    (net (code "35") (name "Net-(U19-EN{slash}SYNC)") (class "Default")
      (node (ref "R102") (pin "2") (pinfunction "2_2") (pintype "passive"))
      (node (ref "R4") (pin "1") (pinfunction "1_1") (pintype "passive"))
      (node (ref "U19") (pin "7") (pinfunction "EN/SYNC_7") (pintype "passive"))
    )
    (net (code "36") (name "Net-(U19-RBOOT)") (class "Default")
      (node (ref "R65") (pin "1") (pinfunction "1_1") (pintype "passive"))
      (node (ref "U19") (pin "13") (pinfunction "RBOOT_13") (pintype "passive"))
    )
    (net (code "37") (name "Net-(U19-RT)") (class "Default")
      (node (ref "R66") (pin "2") (pinfunction "2_2") (pintype "passive"))
      (node (ref "U19") (pin "6") (pinfunction "RT_6") (pintype "passive"))
    )
    (net (code "38") (name "Net-(U19-VCC)") (class "Default")
      (node (ref "C72") (pin "1") (pinfunction "1_1") (pintype "passive"))
      (node (ref "U19") (pin "2") (pinfunction "VCC_2") (pintype "passive"))
    )
    (net (code "39") (name "Net-(U20-A0)") (class "Default")
      (node (ref "R58") (pin "1") (pinfunction "1_1") (pintype "passive"))
      (node (ref "R8") (pin "1") (pinfunction "1_1") (pintype "passive"))
      (node (ref "U20") (pin "1") (pinfunction "A0_1") (pintype "passive"))
    )
    (net (code "40") (name "Net-(U20-A1)") (class "Default")
      (node (ref "R59") (pin "1") (pinfunction "1_1") (pintype "passive"))
      (node (ref "R74") (pin "1") (pinfunction "1_1") (pintype "passive"))
      (node (ref "U20") (pin "2") (pinfunction "A1_2") (pintype "passive"))
    )
    (net (code "41") (name "Net-(U21-IN1+)") (class "Default")
      (node (ref "R10") (pin "1") (pinfunction "1_1") (pintype "passive"))
      (node (ref "R11") (pin "2") (pinfunction "2_2") (pintype "passive"))
      (node (ref "U21") (pin "3") (pinfunction "IN1+_3") (pintype "input"))
    )
    (net (code "42") (name "Net-(U21-IN1-)") (class "Default")
      (node (ref "U21") (pin "4") (pinfunction "IN1-_4") (pintype "input"))
      (node (ref "U21") (pin "5") (pinfunction "VREF_5") (pintype "power_in"))
    )
    (net (code "43") (name "unconnected-(U19-PGOOD-Pad5)") (class "Default")
      (node (ref "U19") (pin "5") (pinfunction "PGOOD_5") (pintype "passive+no_connect"))
    )
    (net (code "44") (name "unconnected-(U20-~{EVENT}-Pad7)") (class "Default")
      (node (ref "U20") (pin "7") (pinfunction "~{EVENT}_7") (pintype "passive+no_connect"))
    )
  )
)
